# WiFi.net
KiCad netlist of a schematic drawn in Altium Designer
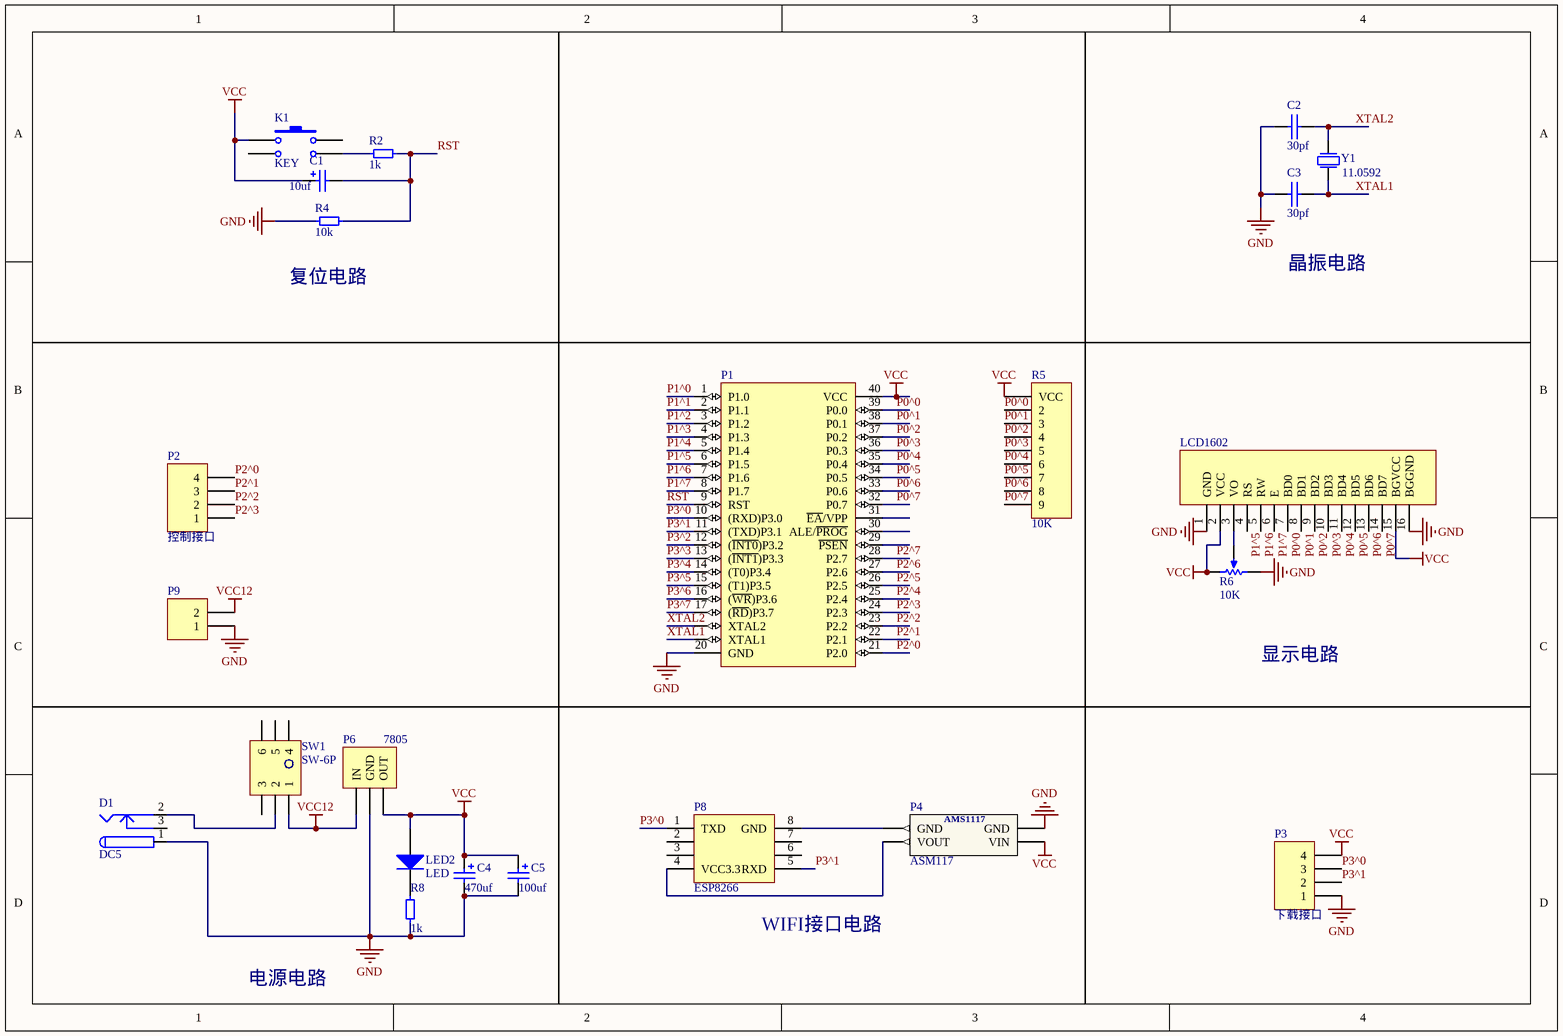
[diagram p0: WiFi小车.SchDoc]

(export (version "E")
  (design (tool "Eeschema 10.0.6"))
  (components
    (comp (ref "C1")
      (value "10uf")
      (footprint "10uf")
      (description "电解电容")
      (libsource (lib "51") (part "C 10uf"))
    )
    (comp (ref "C2") (value "30pf") (footprint "C") (description "贴片电容") (libsource (lib "51") (part "C")))
    (comp (ref "C3") (value "30pf") (footprint "C") (description "贴片电容") (libsource (lib "51") (part "C")))
    (comp (ref "C4")
      (value "470uf")
      (footprint "C1000uf")
      (description "电容")
      (libsource (lib "24V TO 5v") (part "C1000uf"))
    )
    (comp (ref "C5")
      (value "100uf")
      (footprint "C1000uf")
      (description "电容")
      (libsource (lib "24V TO 5v") (part "C1000uf"))
    )
    (comp (ref "D1") (value "DC5") (footprint "DC5") (description "电源接口") (libsource (lib "51") (part "DC5")))
    (comp (ref "K1") (value "KEY") (footprint "KEY") (description "复位按键") (libsource (lib "51") (part "KEY")))
    (comp (ref "LCD1602")
      (value "LCD1602")
      (footprint "LCD1602")
      (description "液晶显示屏")
      (libsource (lib "51") (part "LCD1602"))
    )
    (comp (ref "LED2") (value "LED") (footprint "LED") (libsource (lib "51") (part "LED")))
    (comp (ref "P1")
      (value "STC12C5A60S2")
      (footprint "STC89C52")
      (description "单片机")
      (libsource (lib "51") (part "STC89C52"))
    )
    (comp (ref "P2") (value "控制接口") (footprint "4H") (libsource (lib "51") (part "4H")))
    (comp (ref "P3") (value "下载接口") (footprint "4H") (libsource (lib "51") (part "4H")))
    (comp (ref "P4")
      (value "ASM117")
      (footprint "3.3V稳压模块")
      (description "稳压模块")
      (libsource (lib "51") (part "ASM117稳压模块"))
    )
    (comp (ref "P6") (value "7805") (footprint "3H") (libsource (lib "51") (part "3H")))
    (comp (ref "P8") (value "ESP8266") (footprint "NRF24L01") (libsource (lib "51") (part "nrf2401")))
    (comp (ref "P9") (value "~") (footprint "2H") (description "驱动接口") (libsource (lib "51") (part "2H")))
    (comp (ref "R2") (value "1k") (footprint "R") (description "电阻") (libsource (lib "51") (part "R")))
    (comp (ref "R4") (value "10k") (footprint "R") (description "电阻") (libsource (lib "51") (part "R")))
    (comp (ref "R5")
      (value "10K")
      (footprint "R 10K*8")
      (description "排阻")
      (libsource (lib "51") (part "R10K*8"))
    )
    (comp (ref "R6")
      (value "10K")
      (footprint "R 10K")
      (description "可调电阻")
      (libsource (lib "51") (part "R10K"))
    )
    (comp (ref "R8") (value "1k") (footprint "R") (description "电阻") (libsource (lib "51") (part "R")))
    (comp (ref "SW1")
      (value "SW-6P")
      (footprint "DCSW")
      (description "电源开关")
      (libsource (lib "51") (part "SW-6P"))
    )
    (comp (ref "Y1")
      (value "11.0592")
      (footprint "crystal")
      (description "晶振")
      (libsource (lib "51") (part "crystal"))
    )
  )
  (nets
    (net (code "1") (name "/P0^0") (class "Default")
      (node (ref "LCD1602") (pin "7") (pinfunction "BD0_7") (pintype "passive"))
      (node (ref "P1") (pin "39") (pinfunction "P0.0_39") (pintype "bidirectional"))
      (node (ref "R5") (pin "2") (pinfunction "2_2") (pintype "passive"))
    )
    (net (code "2") (name "/P0^1") (class "Default")
      (node (ref "LCD1602") (pin "8") (pinfunction "BD1_8") (pintype "passive"))
      (node (ref "P1") (pin "38") (pinfunction "P0.1_38") (pintype "bidirectional"))
      (node (ref "R5") (pin "3") (pinfunction "3_3") (pintype "passive"))
    )
    (net (code "3") (name "/P0^2") (class "Default")
      (node (ref "LCD1602") (pin "9") (pinfunction "BD2_9") (pintype "passive"))
      (node (ref "P1") (pin "37") (pinfunction "P0.2_37") (pintype "bidirectional"))
      (node (ref "R5") (pin "4") (pinfunction "4_4") (pintype "passive"))
    )
    (net (code "4") (name "/P0^3") (class "Default")
      (node (ref "LCD1602") (pin "10") (pinfunction "BD3_10") (pintype "passive"))
      (node (ref "P1") (pin "36") (pinfunction "P0.3_36") (pintype "bidirectional"))
      (node (ref "R5") (pin "5") (pinfunction "5_5") (pintype "passive"))
    )
    (net (code "5") (name "/P0^4") (class "Default")
      (node (ref "LCD1602") (pin "11") (pinfunction "BD4_11") (pintype "passive"))
      (node (ref "P1") (pin "35") (pinfunction "P0.4_35") (pintype "bidirectional"))
      (node (ref "R5") (pin "6") (pinfunction "6_6") (pintype "passive"))
    )
    (net (code "6") (name "/P0^5") (class "Default")
      (node (ref "LCD1602") (pin "12") (pinfunction "BD5_12") (pintype "passive"))
      (node (ref "P1") (pin "34") (pinfunction "P0.5_34") (pintype "bidirectional"))
      (node (ref "R5") (pin "7") (pinfunction "7_7") (pintype "passive"))
    )
    (net (code "7") (name "/P0^6") (class "Default")
      (node (ref "LCD1602") (pin "13") (pinfunction "BD6_13") (pintype "passive"))
      (node (ref "P1") (pin "33") (pinfunction "P0.6_33") (pintype "bidirectional"))
      (node (ref "R5") (pin "8") (pinfunction "8_8") (pintype "passive"))
    )
    (net (code "8") (name "/P0^7") (class "Default")
      (node (ref "LCD1602") (pin "14") (pinfunction "BD7_14") (pintype "passive"))
      (node (ref "P1") (pin "32") (pinfunction "P0.7_32") (pintype "bidirectional"))
      (node (ref "R5") (pin "9") (pinfunction "9_9") (pintype "passive"))
    )
    (net (code "9") (name "/P1^0") (class "Default")
      (node (ref "P1") (pin "1") (pinfunction "P1.0_1") (pintype "bidirectional"))
    )
    (net (code "10") (name "/P1^1") (class "Default")
      (node (ref "P1") (pin "2") (pinfunction "P1.1_2") (pintype "bidirectional"))
    )
    (net (code "11") (name "/P1^2") (class "Default")
      (node (ref "P1") (pin "3") (pinfunction "P1.2_3") (pintype "bidirectional"))
    )
    (net (code "12") (name "/P1^3") (class "Default")
      (node (ref "P1") (pin "4") (pinfunction "P1.3_4") (pintype "bidirectional"))
    )
    (net (code "13") (name "/P1^4") (class "Default")
      (node (ref "P1") (pin "5") (pinfunction "P1.4_5") (pintype "bidirectional"))
    )
    (net (code "14") (name "/P1^5") (class "Default")
      (node (ref "LCD1602") (pin "4") (pinfunction "RS_4") (pintype "passive"))
      (node (ref "P1") (pin "6") (pinfunction "P1.5_6") (pintype "bidirectional"))
    )
    (net (code "15") (name "/P1^6") (class "Default")
      (node (ref "LCD1602") (pin "5") (pinfunction "RW_5") (pintype "passive"))
      (node (ref "P1") (pin "7") (pinfunction "P1.6_7") (pintype "bidirectional"))
    )
    (net (code "16") (name "/P1^7") (class "Default")
      (node (ref "LCD1602") (pin "6") (pinfunction "E_6") (pintype "passive"))
      (node (ref "P1") (pin "8") (pinfunction "P1.7_8") (pintype "bidirectional"))
    )
    (net (code "17") (name "/P2^0") (class "Default")
      (node (ref "P1") (pin "21") (pinfunction "P2.0_21") (pintype "bidirectional"))
      (node (ref "P2") (pin "4") (pinfunction "4_4") (pintype "passive"))
    )
    (net (code "18") (name "/P2^1") (class "Default")
      (node (ref "P1") (pin "22") (pinfunction "P2.1_22") (pintype "bidirectional"))
      (node (ref "P2") (pin "3") (pinfunction "3_3") (pintype "passive"))
    )
    (net (code "19") (name "/P2^2") (class "Default")
      (node (ref "P1") (pin "23") (pinfunction "P2.2_23") (pintype "bidirectional"))
      (node (ref "P2") (pin "2") (pinfunction "2_2") (pintype "passive"))
    )
    (net (code "20") (name "/P2^3") (class "Default")
      (node (ref "P1") (pin "24") (pinfunction "P2.3_24") (pintype "bidirectional"))
      (node (ref "P2") (pin "1") (pinfunction "1_1") (pintype "passive"))
    )
    (net (code "21") (name "/P2^4") (class "Default")
      (node (ref "P1") (pin "25") (pinfunction "P2.4_25") (pintype "bidirectional"))
    )
    (net (code "22") (name "/P2^5") (class "Default")
      (node (ref "P1") (pin "26") (pinfunction "P2.5_26") (pintype "bidirectional"))
    )
    (net (code "23") (name "/P2^6") (class "Default")
      (node (ref "P1") (pin "27") (pinfunction "P2.6_27") (pintype "bidirectional"))
    )
    (net (code "24") (name "/P2^7") (class "Default")
      (node (ref "P1") (pin "28") (pinfunction "P2.7_28") (pintype "bidirectional"))
    )
    (net (code "25") (name "/P3^0") (class "Default")
      (node (ref "P1") (pin "10") (pinfunction "(RXD)P3.0_10") (pintype "bidirectional"))
      (node (ref "P3") (pin "3") (pinfunction "3_3") (pintype "passive"))
      (node (ref "P8") (pin "1") (pinfunction "TXD_1") (pintype "passive"))
    )
    (net (code "26") (name "/P3^1") (class "Default")
      (node (ref "P1") (pin "11") (pinfunction "(TXD)P3.1_11") (pintype "bidirectional"))
      (node (ref "P3") (pin "2") (pinfunction "2_2") (pintype "passive"))
      (node (ref "P8") (pin "5") (pinfunction "RXD_5") (pintype "passive"))
    )
    (net (code "27") (name "/P3^2") (class "Default")
      (node (ref "P1") (pin "12") (pinfunction "(~{INT0})P3.2_12") (pintype "bidirectional"))
    )
    (net (code "28") (name "/P3^3") (class "Default")
      (node (ref "P1") (pin "13") (pinfunction "(~{INT1})P3.3_13") (pintype "bidirectional"))
    )
    (net (code "29") (name "/P3^4") (class "Default")
      (node (ref "P1") (pin "14") (pinfunction "(T0)P3.4_14") (pintype "bidirectional"))
    )
    (net (code "30") (name "/P3^5") (class "Default")
      (node (ref "P1") (pin "15") (pinfunction "(T1)P3.5_15") (pintype "bidirectional"))
    )
    (net (code "31") (name "/P3^6") (class "Default")
      (node (ref "P1") (pin "16") (pinfunction "(~{WR})P3.6_16") (pintype "bidirectional"))
    )
    (net (code "32") (name "/P3^7") (class "Default")
      (node (ref "P1") (pin "17") (pinfunction "(~{RD})P3.7_17") (pintype "bidirectional"))
    )
    (net (code "33") (name "/RST") (class "Default")
      (node (ref "C1") (pin "2") (pinfunction "2_2") (pintype "passive"))
      (node (ref "P1") (pin "9") (pinfunction "RST_9") (pintype "bidirectional"))
      (node (ref "R2") (pin "2") (pinfunction "2_2") (pintype "passive"))
      (node (ref "R4") (pin "2") (pinfunction "2_2") (pintype "passive"))
    )
    (net (code "34") (name "/XTAL1") (class "Default")
      (node (ref "C3") (pin "1") (pinfunction "1_1") (pintype "passive"))
      (node (ref "P1") (pin "19") (pinfunction "XTAL1_19") (pintype "bidirectional"))
      (node (ref "Y1") (pin "2") (pinfunction "P2_2") (pintype "passive"))
    )
    (net (code "35") (name "/XTAL2") (class "Default")
      (node (ref "C2") (pin "1") (pinfunction "1_1") (pintype "passive"))
      (node (ref "P1") (pin "18") (pinfunction "XTAL2_18") (pintype "bidirectional"))
      (node (ref "Y1") (pin "1") (pinfunction "P1_1") (pintype "passive"))
    )
    (net (code "36") (name "GND") (class "Default")
      (node (ref "C2") (pin "2") (pinfunction "2_2") (pintype "passive"))
      (node (ref "C3") (pin "2") (pinfunction "2_2") (pintype "passive"))
      (node (ref "C4") (pin "2") (pinfunction "2_2") (pintype "passive"))
      (node (ref "C5") (pin "2") (pinfunction "2_2") (pintype "passive"))
      (node (ref "D1") (pin "1") (pinfunction "1_1") (pintype "passive"))
      (node (ref "LCD1602") (pin "1") (pinfunction "GND_1") (pintype "passive"))
      (node (ref "LCD1602") (pin "16") (pinfunction "BGGND_16") (pintype "passive"))
      (node (ref "P1") (pin "20") (pinfunction "GND_20") (pintype "power_in"))
      (node (ref "P3") (pin "1") (pinfunction "1_1") (pintype "passive"))
      (node (ref "P4") (pin "1") (pinfunction "GND_1") (pintype "power_in"))
      (node (ref "P6") (pin "2") (pinfunction "GND_2") (pintype "passive"))
      (node (ref "P9") (pin "1") (pinfunction "1_1") (pintype "passive"))
      (node (ref "R4") (pin "1") (pinfunction "1_1") (pintype "passive"))
      (node (ref "R6") (pin "1") (pinfunction "TOP_1") (pintype "passive"))
      (node (ref "R8") (pin "1") (pinfunction "1_1") (pintype "passive"))
    )
    (net (code "37") (name "Net-(D1-Pad2)") (class "Default")
      (node (ref "D1") (pin "2") (pinfunction "2_2") (pintype "passive"))
      (node (ref "SW1") (pin "2") (pinfunction "2_2") (pintype "passive"))
    )
    (net (code "38") (name "Net-(K1-Pad3)") (class "Default")
      (node (ref "K1") (pin "3") (pinfunction "3_3") (pintype "passive"))
      (node (ref "R2") (pin "1") (pinfunction "1_1") (pintype "passive"))
    )
    (net (code "39") (name "Net-(LCD1602-VO)") (class "Default")
      (node (ref "LCD1602") (pin "3") (pinfunction "VO_3") (pintype "passive"))
      (node (ref "R6") (pin "2") (pinfunction "BOT_2") (pintype "passive"))
    )
    (net (code "40") (name "Net-(LED2-K)") (class "Default")
      (node (ref "LED2") (pin "2") (pinfunction "K_2") (pintype "passive"))
      (node (ref "R8") (pin "2") (pinfunction "2_2") (pintype "passive"))
    )
    (net (code "41") (name "Net-(P4-VOUT)") (class "Default")
      (node (ref "P4") (pin "4") (pinfunction "VOUT_4") (pintype "output"))
      (node (ref "P8") (pin "4") (pinfunction "VCC3.3_4") (pintype "passive"))
    )
    (net (code "42") (name "Net-(P8-GND)") (class "Default")
      (node (ref "P4") (pin "3") (pinfunction "GND_3") (pintype "output"))
      (node (ref "P8") (pin "8") (pinfunction "GND_8") (pintype "passive"))
    )
    (net (code "43") (name "VCC") (class "Default")
      (node (ref "C1") (pin "1") (pinfunction "1_1") (pintype "passive"))
      (node (ref "C4") (pin "1") (pinfunction "1_1") (pintype "passive"))
      (node (ref "C5") (pin "1") (pinfunction "1_1") (pintype "passive"))
      (node (ref "K1") (pin "1") (pinfunction "1_1") (pintype "passive"))
      (node (ref "LCD1602") (pin "15") (pinfunction "BGVCC_15") (pintype "passive"))
      (node (ref "LCD1602") (pin "2") (pinfunction "VCC_2") (pintype "passive"))
      (node (ref "LED2") (pin "1") (pinfunction "A_1") (pintype "passive"))
      (node (ref "P1") (pin "40") (pinfunction "VCC_40") (pintype "power_in"))
      (node (ref "P3") (pin "4") (pinfunction "4_4") (pintype "passive"))
      (node (ref "P4") (pin "2") (pinfunction "VIN_2") (pintype "power_in"))
      (node (ref "P6") (pin "3") (pinfunction "OUT_3") (pintype "passive"))
      (node (ref "R5") (pin "1") (pinfunction "VCC_1") (pintype "passive"))
      (node (ref "R6") (pin "3") (pinfunction "TAP_3") (pintype "passive"))
    )
    (net (code "44") (name "VCC12") (class "Default")
      (node (ref "P6") (pin "1") (pinfunction "IN_1") (pintype "passive"))
      (node (ref "P9") (pin "2") (pinfunction "2_2") (pintype "passive"))
      (node (ref "SW1") (pin "1") (pinfunction "1_1") (pintype "passive"))
    )
    (net (code "45") (name "unconnected-(D1-Pad3)") (class "Default")
      (node (ref "D1") (pin "3") (pinfunction "3_3") (pintype "passive"))
    )
    (net (code "46") (name "unconnected-(K1-Pad2)") (class "Default")
      (node (ref "K1") (pin "2") (pinfunction "2_2") (pintype "passive"))
    )
    (net (code "47") (name "unconnected-(K1-Pad4)") (class "Default")
      (node (ref "K1") (pin "4") (pinfunction "4_4") (pintype "passive"))
    )
    (net (code "48") (name "unconnected-(P1-ALE{slash}~{PROG}-Pad30)") (class "Default")
      (node (ref "P1") (pin "30") (pinfunction "ALE/~{PROG}_30") (pintype "bidirectional"))
    )
    (net (code "49") (name "unconnected-(P1-~{EA}{slash}VPP-Pad31)") (class "Default")
      (node (ref "P1") (pin "31") (pinfunction "~{EA}/VPP_31") (pintype "power_in"))
    )
    (net (code "50") (name "unconnected-(P1-~{PSEN}-Pad29)") (class "Default")
      (node (ref "P1") (pin "29") (pinfunction "~{PSEN}_29") (pintype "bidirectional"))
    )
    (net (code "51") (name "unconnected-(P8-Pad2)") (class "Default")
      (node (ref "P8") (pin "2") (pintype "passive"))
    )
    (net (code "52") (name "unconnected-(P8-Pad3)") (class "Default")
      (node (ref "P8") (pin "3") (pintype "passive"))
    )
    (net (code "53") (name "unconnected-(P8-Pad6)") (class "Default")
      (node (ref "P8") (pin "6") (pintype "passive"))
    )
    (net (code "54") (name "unconnected-(P8-Pad7)") (class "Default")
      (node (ref "P8") (pin "7") (pintype "passive"))
    )
    (net (code "55") (name "unconnected-(SW1-Pad3)") (class "Default")
      (node (ref "SW1") (pin "3") (pinfunction "3_3") (pintype "passive"))
    )
    (net (code "56") (name "unconnected-(SW1-Pad4)") (class "Default")
      (node (ref "SW1") (pin "4") (pinfunction "4_4") (pintype "passive"))
    )
    (net (code "57") (name "unconnected-(SW1-Pad5)") (class "Default")
      (node (ref "SW1") (pin "5") (pinfunction "5_5") (pintype "passive"))
    )
    (net (code "58") (name "unconnected-(SW1-Pad6)") (class "Default")
      (node (ref "SW1") (pin "6") (pinfunction "6_6") (pintype "passive"))
    )
  )
)
